# T08-TxClicker.net
KiCad netlist of a schematic drawn in EAGLE
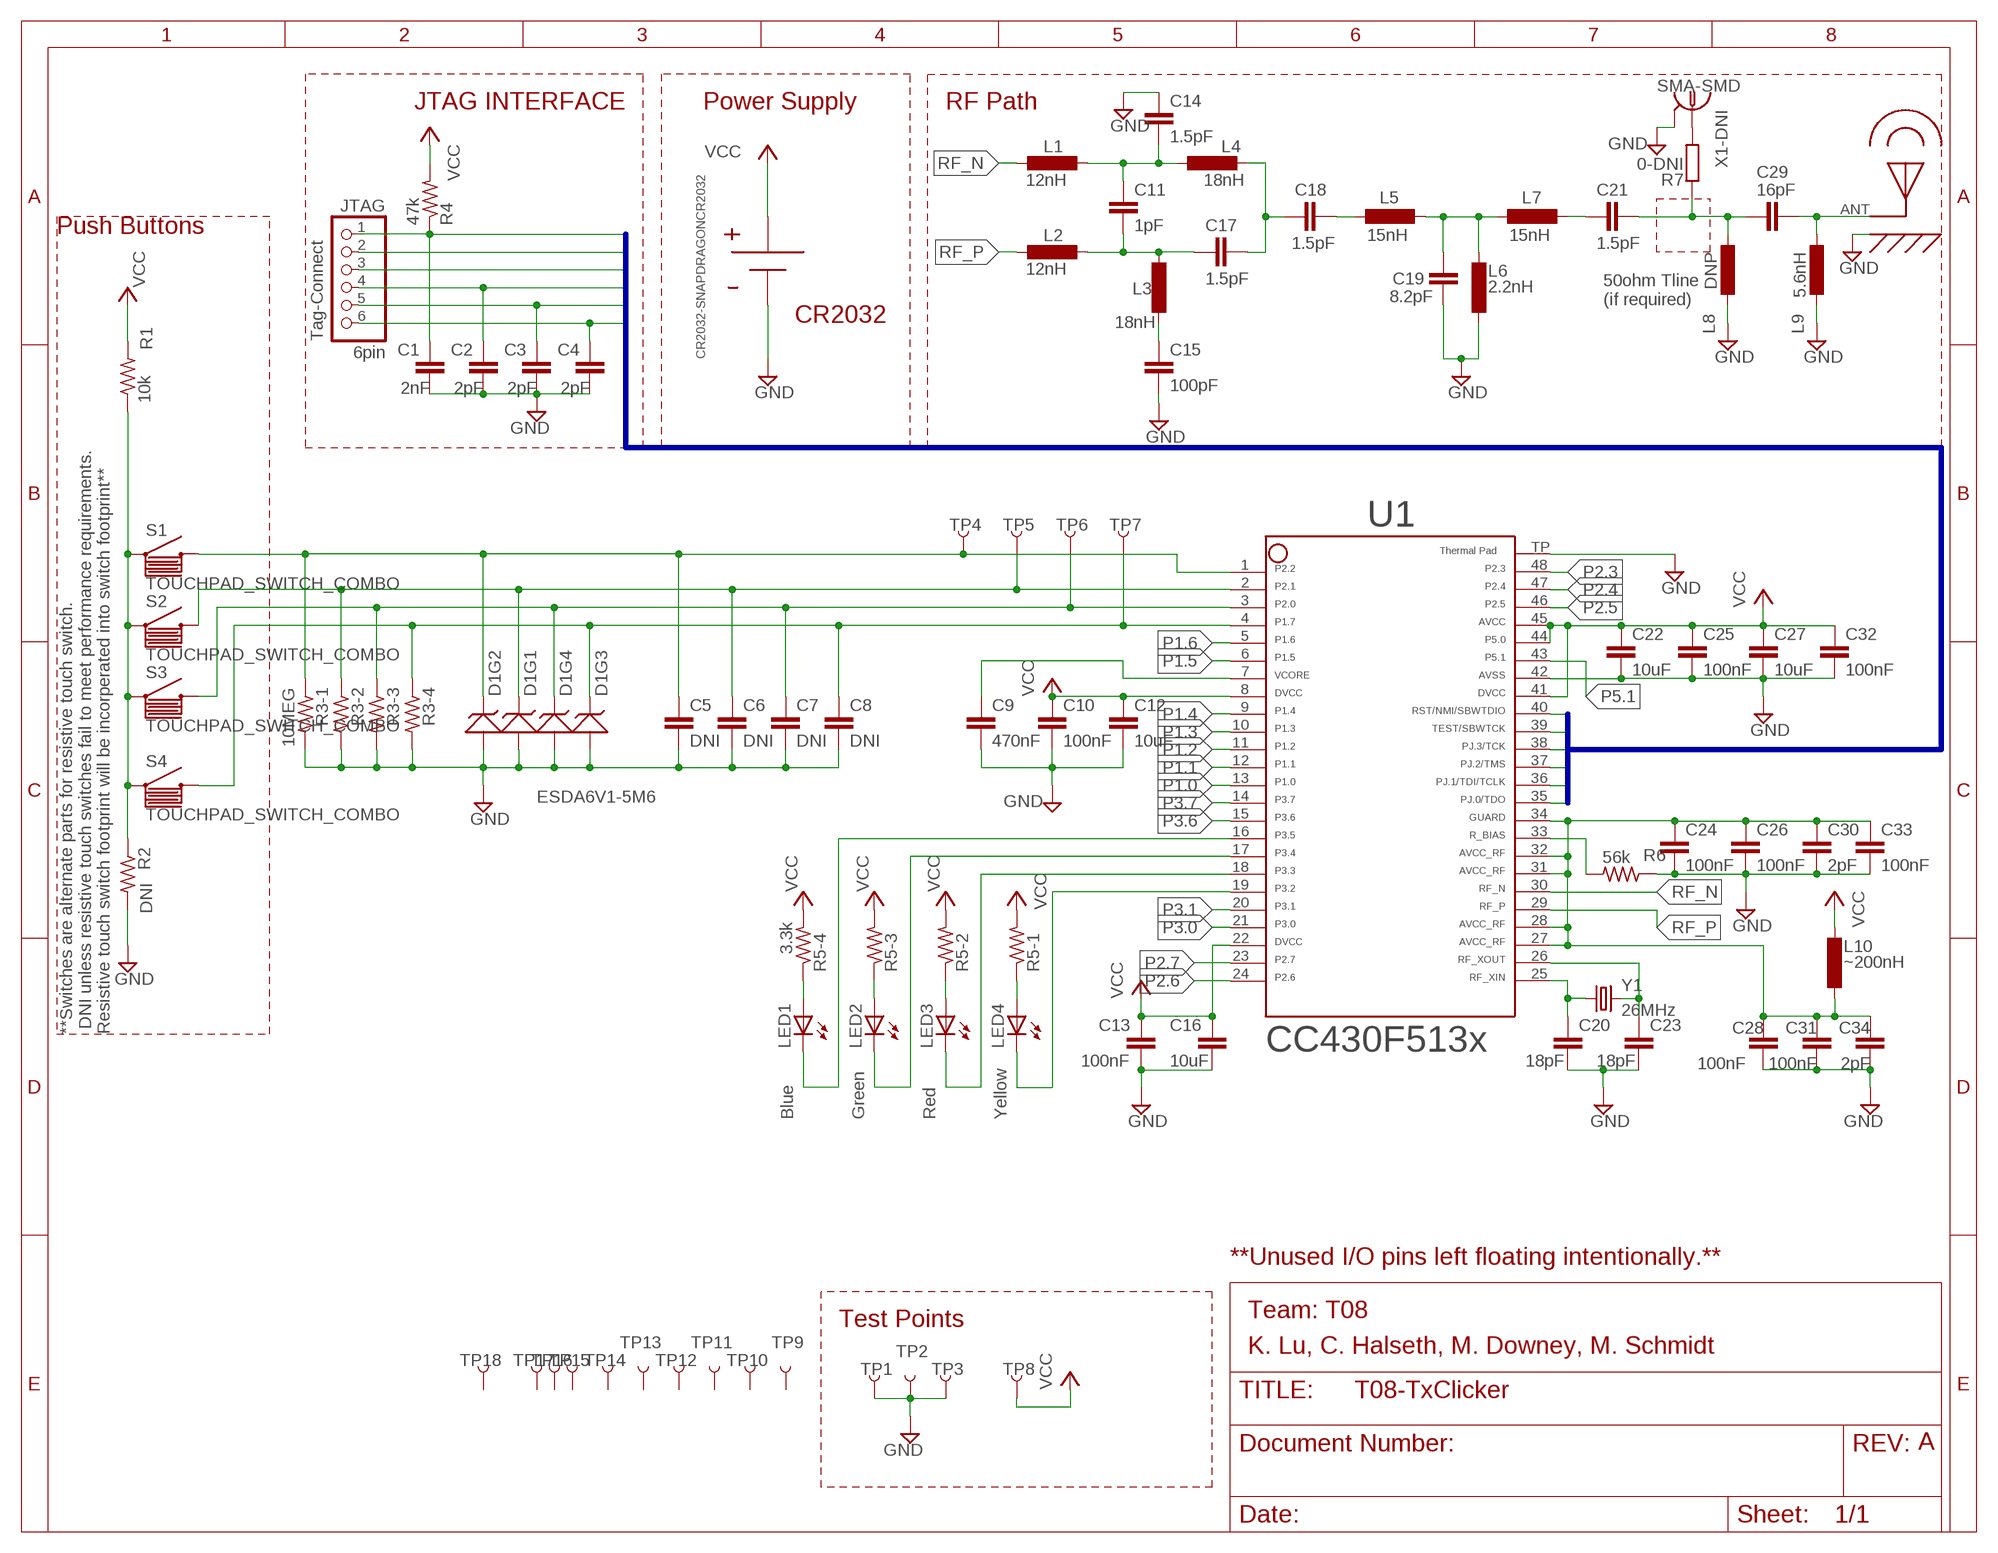
[diagram p0: schematic, sheet 1]

(export (version "E")
  (design (tool "Eeschema 10.0.6"))
  (components
    (comp (ref "C1")
      (value "2nF")
      (footprint "eagle-import:C0603")
      (libsource (lib "eagle-import") (part "C0603"))
    )
    (comp (ref "C2")
      (value "2pF")
      (footprint "eagle-import:C0603")
      (libsource (lib "eagle-import") (part "C0603"))
    )
    (comp (ref "C3")
      (value "2pF")
      (footprint "eagle-import:C0603")
      (libsource (lib "eagle-import") (part "C0603"))
    )
    (comp (ref "C4")
      (value "2pF")
      (footprint "eagle-import:C0603")
      (libsource (lib "eagle-import") (part "C0603"))
    )
    (comp (ref "C5")
      (value "DNI")
      (footprint "eagle-import:C0603")
      (libsource (lib "eagle-import") (part "C-EUC0603"))
    )
    (comp (ref "C6")
      (value "DNI")
      (footprint "eagle-import:C0603")
      (libsource (lib "eagle-import") (part "C-EUC0603"))
    )
    (comp (ref "C7")
      (value "DNI")
      (footprint "eagle-import:C0603")
      (libsource (lib "eagle-import") (part "C-EUC0603"))
    )
    (comp (ref "C8")
      (value "DNI")
      (footprint "eagle-import:C0603")
      (libsource (lib "eagle-import") (part "C-EUC0603"))
    )
    (comp (ref "C9")
      (value "470nF")
      (footprint "eagle-import:C0603")
      (libsource (lib "eagle-import") (part "C-EUC0603"))
    )
    (comp (ref "C10")
      (value "100nF")
      (footprint "eagle-import:C0603")
      (libsource (lib "eagle-import") (part "C-EUC0603"))
    )
    (comp (ref "C11")
      (value "1pF")
      (footprint "eagle-import:C0402")
      (libsource (lib "eagle-import") (part "C0402"))
    )
    (comp (ref "C12")
      (value "10uF")
      (footprint "eagle-import:C0805")
      (libsource (lib "eagle-import") (part "C-EUC0805"))
    )
    (comp (ref "C13")
      (value "100nF")
      (footprint "eagle-import:C0603")
      (libsource (lib "eagle-import") (part "C-EUC0603"))
    )
    (comp (ref "C14")
      (value "1.5pF")
      (footprint "eagle-import:C0402")
      (libsource (lib "eagle-import") (part "C0402"))
    )
    (comp (ref "C15")
      (value "100pF")
      (footprint "eagle-import:C0402")
      (libsource (lib "eagle-import") (part "C0402"))
    )
    (comp (ref "C16")
      (value "10uF")
      (footprint "eagle-import:C0805")
      (libsource (lib "eagle-import") (part "C-EUC0805"))
    )
    (comp (ref "C17")
      (value "1.5pF")
      (footprint "eagle-import:C0402")
      (libsource (lib "eagle-import") (part "C0402"))
    )
    (comp (ref "C18")
      (value "1.5pF")
      (footprint "eagle-import:C0402")
      (libsource (lib "eagle-import") (part "C0402"))
    )
    (comp (ref "C19")
      (value "8.2pF")
      (footprint "eagle-import:C0402")
      (libsource (lib "eagle-import") (part "C0402"))
    )
    (comp (ref "C20")
      (value "18pF")
      (footprint "eagle-import:C0402")
      (libsource (lib "eagle-import") (part "C-EUC0402"))
    )
    (comp (ref "C21")
      (value "1.5pF")
      (footprint "eagle-import:C0402")
      (libsource (lib "eagle-import") (part "C0402"))
    )
    (comp (ref "C22")
      (value "10uF")
      (footprint "eagle-import:C0805")
      (libsource (lib "eagle-import") (part "C-EUC0805"))
    )
    (comp (ref "C23")
      (value "18pF")
      (footprint "eagle-import:C0402")
      (libsource (lib "eagle-import") (part "C-EUC0402"))
    )
    (comp (ref "C24")
      (value "100nF")
      (footprint "eagle-import:C0603")
      (libsource (lib "eagle-import") (part "C-EUC0603"))
    )
    (comp (ref "C25")
      (value "100nF")
      (footprint "eagle-import:C0603")
      (libsource (lib "eagle-import") (part "C-EUC0603"))
    )
    (comp (ref "C26")
      (value "100nF")
      (footprint "eagle-import:C0603")
      (libsource (lib "eagle-import") (part "C-EUC0603"))
    )
    (comp (ref "C27")
      (value "10uF")
      (footprint "eagle-import:C0805")
      (libsource (lib "eagle-import") (part "C-EUC0805"))
    )
    (comp (ref "C28")
      (value "100nF")
      (footprint "eagle-import:C0603")
      (libsource (lib "eagle-import") (part "C-EUC0603"))
    )
    (comp (ref "C29")
      (value "16pF")
      (footprint "eagle-import:C0402")
      (libsource (lib "eagle-import") (part "C0402"))
    )
    (comp (ref "C30")
      (value "2pF")
      (footprint "eagle-import:C0603")
      (libsource (lib "eagle-import") (part "C-EUC0603"))
    )
    (comp (ref "C31")
      (value "100nF")
      (footprint "eagle-import:C0603")
      (libsource (lib "eagle-import") (part "C-EUC0603"))
    )
    (comp (ref "C32")
      (value "100nF")
      (footprint "eagle-import:C0603")
      (libsource (lib "eagle-import") (part "C-EUC0603"))
    )
    (comp (ref "C33")
      (value "100nF")
      (footprint "eagle-import:C0603")
      (libsource (lib "eagle-import") (part "C-EUC0603"))
    )
    (comp (ref "C34")
      (value "2pF")
      (footprint "eagle-import:C0603")
      (libsource (lib "eagle-import") (part "C-EUC0603"))
    )
    (comp (ref "D1")
      (value "ESDA6V1-5M6")
      (footprint "eagle-import:5X-TVS")
      (libsource (lib "eagle-import") (part "ESDA6V1-5M6"))
    )
    (comp (ref "JTAG")
      (value "6pin")
      (footprint "eagle-import:1X06")
      (libsource (lib "eagle-import") (part "PINHD-1X6"))
    )
    (comp (ref "L1")
      (value "12nH")
      (footprint "eagle-import:L0402")
      (libsource (lib "eagle-import") (part "LL0402"))
    )
    (comp (ref "L2")
      (value "12nH")
      (footprint "eagle-import:L0402")
      (libsource (lib "eagle-import") (part "LL0402"))
    )
    (comp (ref "L3")
      (value "18nH")
      (footprint "eagle-import:L0402")
      (libsource (lib "eagle-import") (part "LL0402"))
    )
    (comp (ref "L4")
      (value "18nH")
      (footprint "eagle-import:L0402")
      (libsource (lib "eagle-import") (part "LL0402"))
    )
    (comp (ref "L5")
      (value "15nH")
      (footprint "eagle-import:L0402")
      (libsource (lib "eagle-import") (part "LL0402"))
    )
    (comp (ref "L6")
      (value "2.2nH")
      (footprint "eagle-import:L0402")
      (libsource (lib "eagle-import") (part "LL0402"))
    )
    (comp (ref "L7")
      (value "15nH")
      (footprint "eagle-import:L0402")
      (libsource (lib "eagle-import") (part "LL0402"))
    )
    (comp (ref "L8")
      (value "DNP")
      (footprint "eagle-import:L0402")
      (libsource (lib "eagle-import") (part "LL0402"))
    )
    (comp (ref "L9")
      (value "5.6nH")
      (footprint "eagle-import:L0402")
      (libsource (lib "eagle-import") (part "LL0402"))
    )
    (comp (ref "L10")
      (value "~200nH")
      (footprint "eagle-import:L0603")
      (libsource (lib "eagle-import") (part "LL0603"))
    )
    (comp (ref "LED1")
      (value "Blue")
      (footprint "eagle-import:CHIP-LED0603")
      (libsource (lib "eagle-import") (part "LEDCHIP-LED0603"))
    )
    (comp (ref "LED2")
      (value "Green")
      (footprint "eagle-import:CHIP-LED0603")
      (libsource (lib "eagle-import") (part "LEDCHIP-LED0603"))
    )
    (comp (ref "LED3")
      (value "Red")
      (footprint "eagle-import:CHIP-LED0603")
      (libsource (lib "eagle-import") (part "LEDCHIP-LED0603"))
    )
    (comp (ref "LED4")
      (value "Yellow")
      (footprint "eagle-import:CHIP-LED0603")
      (libsource (lib "eagle-import") (part "LEDCHIP-LED0603"))
    )
    (comp (ref "R1")
      (value "10k")
      (footprint "eagle-import:R0603")
      (libsource (lib "eagle-import") (part "R-US_R0603"))
    )
    (comp (ref "R2")
      (value "DNI")
      (footprint "eagle-import:R0603")
      (libsource (lib "eagle-import") (part "R-US_R0603"))
    )
    (comp (ref "R3")
      (value "10MEG")
      (footprint "eagle-import:2012(4_RES)")
      (libsource (lib "eagle-import") (part "R603X42012"))
    )
    (comp (ref "R4")
      (value "47k")
      (footprint "eagle-import:R0603")
      (libsource (lib "eagle-import") (part "R-US_R0603"))
    )
    (comp (ref "R5")
      (value "3.3k")
      (footprint "eagle-import:2012(4_RES)")
      (libsource (lib "eagle-import") (part "R603X42012"))
    )
    (comp (ref "R6")
      (value "56k")
      (footprint "eagle-import:R0603")
      (libsource (lib "eagle-import") (part "R-US_R0603"))
    )
    (comp (ref "R7")
      (value "0-DNI")
      (footprint "eagle-import:R0603")
      (libsource (lib "eagle-import") (part "R0603"))
    )
    (comp (ref "S1")
      (value "TOUCHPAD_SWITCH_COMBO")
      (footprint "eagle-import:TACTILE-PTH-12MM")
      (libsource (lib "eagle-import") (part "TOUCHPAD_SWITCH_COMBO"))
    )
    (comp (ref "S2")
      (value "TOUCHPAD_SWITCH_COMBO")
      (footprint "eagle-import:TACTILE-PTH-12MM")
      (libsource (lib "eagle-import") (part "TOUCHPAD_SWITCH_COMBO"))
    )
    (comp (ref "S3")
      (value "TOUCHPAD_SWITCH_COMBO")
      (footprint "eagle-import:TACTILE-PTH-12MM")
      (libsource (lib "eagle-import") (part "TOUCHPAD_SWITCH_COMBO"))
    )
    (comp (ref "S4")
      (value "TOUCHPAD_SWITCH_COMBO")
      (footprint "eagle-import:TACTILE-PTH-12MM")
      (libsource (lib "eagle-import") (part "TOUCHPAD_SWITCH_COMBO"))
    )
    (comp (ref "TP1")
      (value "TEST-POINT3")
      (footprint "eagle-import:PAD.03X.03")
      (libsource (lib "eagle-import") (part "TEST-POINT3"))
    )
    (comp (ref "TP2")
      (value "TEST-POINT3")
      (footprint "eagle-import:PAD.03X.03")
      (libsource (lib "eagle-import") (part "TEST-POINT3"))
    )
    (comp (ref "TP3")
      (value "TEST-POINT3")
      (footprint "eagle-import:PAD.03X.03")
      (libsource (lib "eagle-import") (part "TEST-POINT3"))
    )
    (comp (ref "TP4")
      (value "TEST-POINT3")
      (footprint "eagle-import:PAD.03X.03")
      (libsource (lib "eagle-import") (part "TEST-POINT3"))
    )
    (comp (ref "TP5")
      (value "TEST-POINT3")
      (footprint "eagle-import:PAD.03X.03")
      (libsource (lib "eagle-import") (part "TEST-POINT3"))
    )
    (comp (ref "TP6")
      (value "TEST-POINT3")
      (footprint "eagle-import:PAD.03X.03")
      (libsource (lib "eagle-import") (part "TEST-POINT3"))
    )
    (comp (ref "TP7")
      (value "TEST-POINT3")
      (footprint "eagle-import:PAD.03X.03")
      (libsource (lib "eagle-import") (part "TEST-POINT3"))
    )
    (comp (ref "TP8")
      (value "TEST-POINT3")
      (footprint "eagle-import:PAD.03X.03")
      (libsource (lib "eagle-import") (part "TEST-POINT3"))
    )
    (comp (ref "TP9")
      (value "TEST-POINT3")
      (footprint "eagle-import:PAD.03X.03")
      (libsource (lib "eagle-import") (part "TEST-POINT3"))
    )
    (comp (ref "TP10")
      (value "TEST-POINT3")
      (footprint "eagle-import:PAD.03X.03")
      (libsource (lib "eagle-import") (part "TEST-POINT3"))
    )
    (comp (ref "TP11")
      (value "TEST-POINT3")
      (footprint "eagle-import:PAD.03X.03")
      (libsource (lib "eagle-import") (part "TEST-POINT3"))
    )
    (comp (ref "TP12")
      (value "TEST-POINT3")
      (footprint "eagle-import:PAD.03X.03")
      (libsource (lib "eagle-import") (part "TEST-POINT3"))
    )
    (comp (ref "TP13")
      (value "TEST-POINT3")
      (footprint "eagle-import:PAD.03X.03")
      (libsource (lib "eagle-import") (part "TEST-POINT3"))
    )
    (comp (ref "TP14")
      (value "TEST-POINT3")
      (footprint "eagle-import:PAD.03X.03")
      (libsource (lib "eagle-import") (part "TEST-POINT3"))
    )
    (comp (ref "TP15")
      (value "TEST-POINT3")
      (footprint "eagle-import:PAD.03X.03")
      (libsource (lib "eagle-import") (part "TEST-POINT3"))
    )
    (comp (ref "TP16")
      (value "TEST-POINT3")
      (footprint "eagle-import:PAD.03X.03")
      (libsource (lib "eagle-import") (part "TEST-POINT3"))
    )
    (comp (ref "TP17")
      (value "TEST-POINT3")
      (footprint "eagle-import:PAD.03X.03")
      (libsource (lib "eagle-import") (part "TEST-POINT3"))
    )
    (comp (ref "TP18")
      (value "TEST-POINT3")
      (footprint "eagle-import:PAD.03X.03")
      (libsource (lib "eagle-import") (part "TEST-POINT3"))
    )
    (comp (ref "U$5")
      (value "CR2032-SNAPDRAGONCR2032")
      (footprint "eagle-import:CR2032-SNAPDRAGON")
      (libsource (lib "eagle-import") (part "CR2032-SNAPDRAGONCR2032"))
    )
    (comp (ref "U$6")
      (value "PCB_ANTENNA_915MHZOSHP")
      (footprint "eagle-import:PCB_ANTENNA_915MHZ")
      (libsource (lib "eagle-import") (part "PCB_ANTENNA_915MHZOSHP"))
    )
    (comp (ref "U1")
      (value "CC430F513X---RGZ48")
      (footprint "eagle-import:RGZ48")
      (libsource (lib "eagle-import") (part "CC430F513X---RGZ48"))
    )
    (comp (ref "X1-DNI")
      (value "SMA-SMD")
      (footprint "eagle-import:SMA-SMD")
      (libsource (lib "eagle-import") (part "SMA-SMD"))
    )
    (comp (ref "Y1")
      (value "26MHz")
      (footprint "eagle-import:CRYSTAL-TXC-7A")
      (libsource (lib "eagle-import") (part "CRYSTALTXC-7A"))
    )
  )
  (nets
    (net (code "1") (name "/PJ.0{slash}TDO") (class "Default")
      (node (ref "C4") (pin "1") (pinfunction "1_1") (pintype "passive"))
      (node (ref "JTAG") (pin "6") (pinfunction "6_6") (pintype "passive"))
      (node (ref "U1") (pin "35") (pinfunction "35_35") (pintype "bidirectional"))
    )
    (net (code "2") (name "/PJ.1{slash}TDI{slash}TCLK") (class "Default")
      (node (ref "C3") (pin "1") (pinfunction "1_1") (pintype "passive"))
      (node (ref "JTAG") (pin "5") (pinfunction "5_5") (pintype "passive"))
      (node (ref "U1") (pin "36") (pinfunction "36_36") (pintype "bidirectional"))
    )
    (net (code "3") (name "/PJ.2{slash}TMS") (class "Default")
      (node (ref "C2") (pin "1") (pinfunction "1_1") (pintype "passive"))
      (node (ref "JTAG") (pin "4") (pinfunction "4_4") (pintype "passive"))
      (node (ref "U1") (pin "37") (pinfunction "37_37") (pintype "bidirectional"))
    )
    (net (code "4") (name "/PJ.3{slash}TCK") (class "Default")
      (node (ref "JTAG") (pin "3") (pinfunction "3_3") (pintype "passive"))
      (node (ref "U1") (pin "38") (pinfunction "38_38") (pintype "bidirectional"))
    )
    (net (code "5") (name "/RST{slash}NMI{slash}SBWTDIO") (class "Default")
      (node (ref "C1") (pin "1") (pinfunction "1_1") (pintype "passive"))
      (node (ref "JTAG") (pin "1") (pinfunction "1_1") (pintype "passive"))
      (node (ref "R4") (pin "1") (pinfunction "1_1") (pintype "passive"))
      (node (ref "U1") (pin "40") (pinfunction "40_40") (pintype "bidirectional"))
    )
    (net (code "6") (name "/TEST{slash}SBWTCK") (class "Default")
      (node (ref "JTAG") (pin "2") (pinfunction "2_2") (pintype "passive"))
      (node (ref "U1") (pin "39") (pinfunction "39_39") (pintype "input"))
    )
    (net (code "7") (name "GND") (class "Default")
      (node (ref "C1") (pin "2") (pinfunction "2_2") (pintype "passive"))
      (node (ref "C10") (pin "2") (pinfunction "2_2") (pintype "passive"))
      (node (ref "C12") (pin "2") (pinfunction "2_2") (pintype "passive"))
      (node (ref "C13") (pin "2") (pinfunction "2_2") (pintype "passive"))
      (node (ref "C14") (pin "P$1") (pinfunction "1_P$1") (pintype "passive"))
      (node (ref "C15") (pin "P$2") (pinfunction "2_P$2") (pintype "passive"))
      (node (ref "C16") (pin "2") (pinfunction "2_2") (pintype "passive"))
      (node (ref "C19") (pin "P$1") (pinfunction "1_P$1") (pintype "passive"))
      (node (ref "C2") (pin "2") (pinfunction "2_2") (pintype "passive"))
      (node (ref "C20") (pin "2") (pinfunction "2_2") (pintype "passive"))
      (node (ref "C22") (pin "2") (pinfunction "2_2") (pintype "passive"))
      (node (ref "C23") (pin "2") (pinfunction "2_2") (pintype "passive"))
      (node (ref "C24") (pin "2") (pinfunction "2_2") (pintype "passive"))
      (node (ref "C25") (pin "2") (pinfunction "2_2") (pintype "passive"))
      (node (ref "C26") (pin "2") (pinfunction "2_2") (pintype "passive"))
      (node (ref "C27") (pin "2") (pinfunction "2_2") (pintype "passive"))
      (node (ref "C28") (pin "2") (pinfunction "2_2") (pintype "passive"))
      (node (ref "C3") (pin "2") (pinfunction "2_2") (pintype "passive"))
      (node (ref "C30") (pin "2") (pinfunction "2_2") (pintype "passive"))
      (node (ref "C31") (pin "2") (pinfunction "2_2") (pintype "passive"))
      (node (ref "C32") (pin "2") (pinfunction "2_2") (pintype "passive"))
      (node (ref "C33") (pin "2") (pinfunction "2_2") (pintype "passive"))
      (node (ref "C34") (pin "2") (pinfunction "2_2") (pintype "passive"))
      (node (ref "C4") (pin "2") (pinfunction "2_2") (pintype "passive"))
      (node (ref "C5") (pin "2") (pinfunction "2_2") (pintype "passive"))
      (node (ref "C6") (pin "2") (pinfunction "2_2") (pintype "passive"))
      (node (ref "C7") (pin "2") (pinfunction "2_2") (pintype "passive"))
      (node (ref "C8") (pin "2") (pinfunction "2_2") (pintype "passive"))
      (node (ref "C9") (pin "2") (pinfunction "2_2") (pintype "passive"))
      (node (ref "D1") (pin "2") (pinfunction "2_2") (pintype "bidirectional"))
      (node (ref "L6") (pin "P$2") (pinfunction "2_P$2") (pintype "passive"))
      (node (ref "L8") (pin "P$1") (pinfunction "1_P$1") (pintype "passive"))
      (node (ref "L9") (pin "P$1") (pinfunction "1_P$1") (pintype "passive"))
      (node (ref "R2") (pin "2") (pinfunction "2_2") (pintype "passive"))
      (node (ref "R3") (pin "2") (pinfunction "2_2") (pintype "passive"))
      (node (ref "R3") (pin "4") (pinfunction "2_4") (pintype "passive"))
      (node (ref "R3") (pin "6") (pinfunction "2_6") (pintype "passive"))
      (node (ref "R3") (pin "8") (pinfunction "2_8") (pintype "passive"))
      (node (ref "R6") (pin "1") (pinfunction "1_1") (pintype "passive"))
      (node (ref "TP1") (pin "P$1") (pinfunction "1_P$1") (pintype "bidirectional"))
      (node (ref "TP2") (pin "P$1") (pinfunction "1_P$1") (pintype "bidirectional"))
      (node (ref "TP3") (pin "P$1") (pinfunction "1_P$1") (pintype "bidirectional"))
      (node (ref "U$5") (pin "V-") (pinfunction "V-_V-") (pintype "power_in"))
      (node (ref "U$6") (pin "GPLANE") (pinfunction "GPLANE_GPLANE") (pintype "power_in"))
      (node (ref "U1") (pin "42") (pinfunction "42_42") (pintype "power_in"))
      (node (ref "U1") (pin "TP") (pinfunction "49_TP") (pintype "power_in"))
      (node (ref "X1-DNI") (pin "2@1") (pinfunction "2_2@1") (pintype "passive"))
      (node (ref "X1-DNI") (pin "2@2") (pinfunction "2_2@2") (pintype "passive"))
      (node (ref "X1-DNI") (pin "2@3") (pinfunction "2_2@3") (pintype "passive"))
      (node (ref "X1-DNI") (pin "2@4") (pinfunction "2_2@4") (pintype "passive"))
      (node (ref "X1-DNI") (pin "2@5") (pinfunction "2_2@5") (pintype "passive"))
      (node (ref "X1-DNI") (pin "2@6") (pinfunction "2_2@6") (pintype "passive"))
    )
    (net (code "8") (name "Net-(C9-Pad1)") (class "Default")
      (node (ref "C9") (pin "1") (pinfunction "1_1") (pintype "passive"))
      (node (ref "U1") (pin "7") (pinfunction "7_7") (pintype "power_in"))
    )
    (net (code "9") (name "Net-(C11-1)") (class "Default")
      (node (ref "C11") (pin "P$1") (pinfunction "1_P$1") (pintype "passive"))
      (node (ref "C14") (pin "P$2") (pinfunction "2_P$2") (pintype "passive"))
      (node (ref "L1") (pin "P$1") (pinfunction "1_P$1") (pintype "passive"))
      (node (ref "L4") (pin "P$2") (pinfunction "2_P$2") (pintype "passive"))
    )
    (net (code "10") (name "Net-(C11-2)") (class "Default")
      (node (ref "C11") (pin "P$2") (pinfunction "2_P$2") (pintype "passive"))
      (node (ref "C17") (pin "P$2") (pinfunction "2_P$2") (pintype "passive"))
      (node (ref "L2") (pin "P$1") (pinfunction "1_P$1") (pintype "passive"))
      (node (ref "L3") (pin "P$1") (pinfunction "1_P$1") (pintype "passive"))
    )
    (net (code "11") (name "Net-(C15-1)") (class "Default")
      (node (ref "C15") (pin "P$1") (pinfunction "1_P$1") (pintype "passive"))
      (node (ref "L3") (pin "P$2") (pinfunction "2_P$2") (pintype "passive"))
    )
    (net (code "12") (name "Net-(C17-1)") (class "Default")
      (node (ref "C17") (pin "P$1") (pinfunction "1_P$1") (pintype "passive"))
      (node (ref "C18") (pin "P$1") (pinfunction "1_P$1") (pintype "passive"))
      (node (ref "L4") (pin "P$1") (pinfunction "1_P$1") (pintype "passive"))
    )
    (net (code "13") (name "Net-(C18-2)") (class "Default")
      (node (ref "C18") (pin "P$2") (pinfunction "2_P$2") (pintype "passive"))
      (node (ref "L5") (pin "P$1") (pinfunction "1_P$1") (pintype "passive"))
    )
    (net (code "14") (name "Net-(C19-2)") (class "Default")
      (node (ref "C19") (pin "P$2") (pinfunction "2_P$2") (pintype "passive"))
      (node (ref "L5") (pin "P$2") (pinfunction "2_P$2") (pintype "passive"))
      (node (ref "L6") (pin "P$1") (pinfunction "1_P$1") (pintype "passive"))
      (node (ref "L7") (pin "P$1") (pinfunction "1_P$1") (pintype "passive"))
    )
    (net (code "15") (name "Net-(C21-1)") (class "Default")
      (node (ref "C21") (pin "P$1") (pinfunction "1_P$1") (pintype "passive"))
      (node (ref "C29") (pin "P$2") (pinfunction "2_P$2") (pintype "passive"))
      (node (ref "L8") (pin "P$2") (pinfunction "2_P$2") (pintype "passive"))
      (node (ref "R7") (pin "1") (pinfunction "1_1") (pintype "passive"))
    )
    (net (code "16") (name "Net-(C21-2)") (class "Default")
      (node (ref "C21") (pin "P$2") (pinfunction "2_P$2") (pintype "passive"))
      (node (ref "L7") (pin "P$2") (pinfunction "2_P$2") (pintype "passive"))
    )
    (net (code "17") (name "Net-(C24-Pad1)") (class "Default")
      (node (ref "C24") (pin "1") (pinfunction "1_1") (pintype "passive"))
      (node (ref "C26") (pin "1") (pinfunction "1_1") (pintype "passive"))
      (node (ref "C28") (pin "1") (pinfunction "1_1") (pintype "passive"))
      (node (ref "C30") (pin "1") (pinfunction "1_1") (pintype "passive"))
      (node (ref "C31") (pin "1") (pinfunction "1_1") (pintype "passive"))
      (node (ref "C33") (pin "1") (pinfunction "1_1") (pintype "passive"))
      (node (ref "C34") (pin "1") (pinfunction "1_1") (pintype "passive"))
      (node (ref "L10") (pin "2") (pinfunction "2_2") (pintype "passive"))
      (node (ref "U1") (pin "27") (pinfunction "27_27") (pintype "power_in"))
      (node (ref "U1") (pin "28") (pinfunction "28_28") (pintype "bidirectional"))
      (node (ref "U1") (pin "31") (pinfunction "31_31") (pintype "power_in"))
      (node (ref "U1") (pin "32") (pinfunction "32_32") (pintype "power_in"))
      (node (ref "U1") (pin "34") (pinfunction "34_34") (pintype "power_in"))
    )
    (net (code "18") (name "Net-(C29-1)") (class "Default")
      (node (ref "C29") (pin "P$1") (pinfunction "1_P$1") (pintype "passive"))
      (node (ref "L9") (pin "P$2") (pinfunction "2_P$2") (pintype "passive"))
      (node (ref "U$6") (pin "ANT") (pinfunction "ANT_ANT") (pintype "input"))
    )
    (net (code "19") (name "Net-(D1B-P$1)") (class "Default")
      (node (ref "C5") (pin "1") (pinfunction "1_1") (pintype "passive"))
      (node (ref "D1") (pin "3") (pinfunction "P$1_3") (pintype "bidirectional"))
      (node (ref "R3") (pin "1") (pinfunction "1_1") (pintype "passive"))
      (node (ref "S1") (pin "3") (pinfunction "2_3") (pintype "passive"))
      (node (ref "TP4") (pin "P$1") (pinfunction "1_P$1") (pintype "bidirectional"))
      (node (ref "U1") (pin "1") (pinfunction "1_1") (pintype "bidirectional"))
    )
    (net (code "20") (name "Net-(D1C-P$1)") (class "Default")
      (node (ref "C8") (pin "1") (pinfunction "1_1") (pintype "passive"))
      (node (ref "D1") (pin "4") (pinfunction "P$1_4") (pintype "bidirectional"))
      (node (ref "R3") (pin "7") (pinfunction "1_7") (pintype "passive"))
      (node (ref "S4") (pin "3") (pinfunction "2_3") (pintype "passive"))
      (node (ref "TP7") (pin "P$1") (pinfunction "1_P$1") (pintype "bidirectional"))
      (node (ref "U1") (pin "4") (pinfunction "4_4") (pintype "bidirectional"))
    )
    (net (code "21") (name "Net-(D1D-P$1)") (class "Default")
      (node (ref "C7") (pin "1") (pinfunction "1_1") (pintype "passive"))
      (node (ref "D1") (pin "5") (pinfunction "P$1_5") (pintype "bidirectional"))
      (node (ref "R3") (pin "5") (pinfunction "1_5") (pintype "passive"))
      (node (ref "S3") (pin "3") (pinfunction "2_3") (pintype "passive"))
      (node (ref "TP6") (pin "P$1") (pinfunction "1_P$1") (pintype "bidirectional"))
      (node (ref "U1") (pin "3") (pinfunction "3_3") (pintype "bidirectional"))
    )
    (net (code "22") (name "Net-(LED1-PadC)") (class "Default")
      (node (ref "LED1") (pin "C") (pinfunction "C_C") (pintype "bidirectional"))
      (node (ref "U1") (pin "16") (pinfunction "16_16") (pintype "bidirectional"))
    )
    (net (code "23") (name "Net-(LED2-PadC)") (class "Default")
      (node (ref "LED2") (pin "C") (pinfunction "C_C") (pintype "bidirectional"))
      (node (ref "U1") (pin "17") (pinfunction "17_17") (pintype "bidirectional"))
    )
    (net (code "24") (name "Net-(LED3-PadC)") (class "Default")
      (node (ref "LED3") (pin "C") (pinfunction "C_C") (pintype "bidirectional"))
      (node (ref "U1") (pin "18") (pinfunction "18_18") (pintype "bidirectional"))
    )
    (net (code "25") (name "Net-(LED4-PadA)") (class "Default")
      (node (ref "LED4") (pin "A") (pinfunction "A_A") (pintype "bidirectional"))
      (node (ref "R5") (pin "1") (pinfunction "1_1") (pintype "passive"))
    )
    (net (code "26") (name "Net-(LED4-PadC)") (class "Default")
      (node (ref "LED4") (pin "C") (pinfunction "C_C") (pintype "bidirectional"))
      (node (ref "U1") (pin "19") (pinfunction "19_19") (pintype "bidirectional"))
    )
    (net (code "27") (name "Net-(R1-Pad1)") (class "Default")
      (node (ref "R1") (pin "1") (pinfunction "1_1") (pintype "passive"))
      (node (ref "R2") (pin "1") (pinfunction "1_1") (pintype "passive"))
      (node (ref "S1") (pin "1") (pinfunction "1_1") (pintype "passive"))
      (node (ref "S2") (pin "1") (pinfunction "1_1") (pintype "passive"))
      (node (ref "S3") (pin "1") (pinfunction "1_1") (pintype "passive"))
      (node (ref "S4") (pin "1") (pinfunction "1_1") (pintype "passive"))
    )
    (net (code "28") (name "Net-(R3B-1)") (class "Default")
      (node (ref "C6") (pin "1") (pinfunction "1_1") (pintype "passive"))
      (node (ref "D1") (pin "1") (pinfunction "1_1") (pintype "bidirectional"))
      (node (ref "R3") (pin "3") (pinfunction "1_3") (pintype "passive"))
      (node (ref "S2") (pin "3") (pinfunction "2_3") (pintype "passive"))
      (node (ref "TP5") (pin "P$1") (pinfunction "1_P$1") (pintype "bidirectional"))
      (node (ref "U1") (pin "2") (pinfunction "2_2") (pintype "bidirectional"))
    )
    (net (code "29") (name "Net-(R5B-1)") (class "Default")
      (node (ref "LED3") (pin "A") (pinfunction "A_A") (pintype "bidirectional"))
      (node (ref "R5") (pin "3") (pinfunction "1_3") (pintype "passive"))
    )
    (net (code "30") (name "Net-(R5C-1)") (class "Default")
      (node (ref "LED2") (pin "A") (pinfunction "A_A") (pintype "bidirectional"))
      (node (ref "R5") (pin "5") (pinfunction "1_5") (pintype "passive"))
    )
    (net (code "31") (name "Net-(R5D-1)") (class "Default")
      (node (ref "LED1") (pin "A") (pinfunction "A_A") (pintype "bidirectional"))
      (node (ref "R5") (pin "7") (pinfunction "1_7") (pintype "passive"))
    )
    (net (code "32") (name "Net-(R6-Pad2)") (class "Default")
      (node (ref "R6") (pin "2") (pinfunction "2_2") (pintype "passive"))
      (node (ref "U1") (pin "33") (pinfunction "33_33") (pintype "power_in"))
    )
    (net (code "33") (name "Net-(R7-Pad2)") (class "Default")
      (node (ref "R7") (pin "2") (pinfunction "2_2") (pintype "passive"))
      (node (ref "X1-DNI") (pin "1") (pinfunction "1_1") (pintype "passive"))
    )
    (net (code "34") (name "Net-(Y1-1)") (class "Default")
      (node (ref "C20") (pin "1") (pinfunction "1_1") (pintype "passive"))
      (node (ref "U1") (pin "25") (pinfunction "25_25") (pintype "input"))
      (node (ref "Y1") (pin "P$1") (pinfunction "1_P$1") (pintype "passive"))
    )
    (net (code "35") (name "Net-(Y1-2)") (class "Default")
      (node (ref "C23") (pin "1") (pinfunction "1_1") (pintype "passive"))
      (node (ref "U1") (pin "26") (pinfunction "26_26") (pintype "output"))
      (node (ref "Y1") (pin "P$2") (pinfunction "2_P$2") (pintype "passive"))
    )
    (net (code "36") (name "P1.0") (class "Default")
      (node (ref "U1") (pin "13") (pinfunction "13_13") (pintype "bidirectional"))
    )
    (net (code "37") (name "P1.1") (class "Default")
      (node (ref "U1") (pin "12") (pinfunction "12_12") (pintype "bidirectional"))
    )
    (net (code "38") (name "P1.2") (class "Default")
      (node (ref "U1") (pin "11") (pinfunction "11_11") (pintype "bidirectional"))
    )
    (net (code "39") (name "P1.3") (class "Default")
      (node (ref "U1") (pin "10") (pinfunction "10_10") (pintype "bidirectional"))
    )
    (net (code "40") (name "P1.4") (class "Default")
      (node (ref "U1") (pin "9") (pinfunction "9_9") (pintype "bidirectional"))
    )
    (net (code "41") (name "P1.5") (class "Default")
      (node (ref "U1") (pin "6") (pinfunction "6_6") (pintype "bidirectional"))
    )
    (net (code "42") (name "P1.6") (class "Default")
      (node (ref "U1") (pin "5") (pinfunction "5_5") (pintype "bidirectional"))
    )
    (net (code "43") (name "P2.3") (class "Default")
      (node (ref "U1") (pin "48") (pinfunction "48_48") (pintype "bidirectional"))
    )
    (net (code "44") (name "P2.4") (class "Default")
      (node (ref "U1") (pin "47") (pinfunction "47_47") (pintype "bidirectional"))
    )
    (net (code "45") (name "P2.5") (class "Default")
      (node (ref "U1") (pin "46") (pinfunction "46_46") (pintype "bidirectional"))
    )
    (net (code "46") (name "P2.6") (class "Default")
      (node (ref "U1") (pin "24") (pinfunction "24_24") (pintype "bidirectional"))
    )
    (net (code "47") (name "P2.7") (class "Default")
      (node (ref "U1") (pin "23") (pinfunction "23_23") (pintype "bidirectional"))
    )
    (net (code "48") (name "P3.0") (class "Default")
      (node (ref "U1") (pin "21") (pinfunction "21_21") (pintype "bidirectional"))
    )
    (net (code "49") (name "P3.1") (class "Default")
      (node (ref "U1") (pin "20") (pinfunction "20_20") (pintype "bidirectional"))
    )
    (net (code "50") (name "P3.6") (class "Default")
      (node (ref "U1") (pin "15") (pinfunction "15_15") (pintype "bidirectional"))
    )
    (net (code "51") (name "P3.7") (class "Default")
      (node (ref "U1") (pin "14") (pinfunction "14_14") (pintype "bidirectional"))
    )
    (net (code "52") (name "P5.1") (class "Default")
      (node (ref "U1") (pin "43") (pinfunction "43_43") (pintype "bidirectional"))
    )
    (net (code "53") (name "RF_N") (class "Default")
      (node (ref "L1") (pin "P$2") (pinfunction "2_P$2") (pintype "passive"))
      (node (ref "U1") (pin "30") (pinfunction "30_30") (pintype "bidirectional"))
    )
    (net (code "54") (name "RF_P") (class "Default")
      (node (ref "L2") (pin "P$2") (pinfunction "2_P$2") (pintype "passive"))
      (node (ref "U1") (pin "29") (pinfunction "29_29") (pintype "bidirectional"))
    )
    (net (code "55") (name "VCC") (class "Default")
      (node (ref "C10") (pin "1") (pinfunction "1_1") (pintype "passive"))
      (node (ref "C12") (pin "1") (pinfunction "1_1") (pintype "passive"))
      (node (ref "C13") (pin "1") (pinfunction "1_1") (pintype "passive"))
      (node (ref "C16") (pin "1") (pinfunction "1_1") (pintype "passive"))
      (node (ref "C22") (pin "1") (pinfunction "1_1") (pintype "passive"))
      (node (ref "C25") (pin "1") (pinfunction "1_1") (pintype "passive"))
      (node (ref "C27") (pin "1") (pinfunction "1_1") (pintype "passive"))
      (node (ref "C32") (pin "1") (pinfunction "1_1") (pintype "passive"))
      (node (ref "L10") (pin "1") (pinfunction "1_1") (pintype "passive"))
      (node (ref "R1") (pin "2") (pinfunction "2_2") (pintype "passive"))
      (node (ref "R4") (pin "2") (pinfunction "2_2") (pintype "passive"))
      (node (ref "R5") (pin "2") (pinfunction "2_2") (pintype "passive"))
      (node (ref "R5") (pin "4") (pinfunction "2_4") (pintype "passive"))
      (node (ref "R5") (pin "6") (pinfunction "2_6") (pintype "passive"))
      (node (ref "R5") (pin "8") (pinfunction "2_8") (pintype "passive"))
      (node (ref "TP8") (pin "P$1") (pinfunction "1_P$1") (pintype "bidirectional"))
      (node (ref "U$5") (pin "V+") (pinfunction "V+_V+") (pintype "passive"))
      (node (ref "U1") (pin "22") (pinfunction "22_22") (pintype "power_in"))
      (node (ref "U1") (pin "41") (pinfunction "41_41") (pintype "power_in"))
      (node (ref "U1") (pin "44") (pinfunction "44_44") (pintype "input"))
      (node (ref "U1") (pin "45") (pinfunction "45_45") (pintype "input"))
      (node (ref "U1") (pin "8") (pinfunction "8_8") (pintype "power_in"))
    )
    (net (code "56") (name "unconnected-(TP9-1-PadP$1)") (class "Default")
      (node (ref "TP9") (pin "P$1") (pinfunction "1_P$1") (pintype "bidirectional"))
    )
    (net (code "57") (name "unconnected-(TP10-1-PadP$1)") (class "Default")
      (node (ref "TP10") (pin "P$1") (pinfunction "1_P$1") (pintype "bidirectional"))
    )
    (net (code "58") (name "unconnected-(TP11-1-PadP$1)") (class "Default")
      (node (ref "TP11") (pin "P$1") (pinfunction "1_P$1") (pintype "bidirectional"))
    )
    (net (code "59") (name "unconnected-(TP12-1-PadP$1)") (class "Default")
      (node (ref "TP12") (pin "P$1") (pinfunction "1_P$1") (pintype "bidirectional"))
    )
    (net (code "60") (name "unconnected-(TP13-1-PadP$1)") (class "Default")
      (node (ref "TP13") (pin "P$1") (pinfunction "1_P$1") (pintype "bidirectional"))
    )
    (net (code "61") (name "unconnected-(TP14-1-PadP$1)") (class "Default")
      (node (ref "TP14") (pin "P$1") (pinfunction "1_P$1") (pintype "bidirectional"))
    )
    (net (code "62") (name "unconnected-(TP15-1-PadP$1)") (class "Default")
      (node (ref "TP15") (pin "P$1") (pinfunction "1_P$1") (pintype "bidirectional"))
    )
    (net (code "63") (name "unconnected-(TP16-1-PadP$1)") (class "Default")
      (node (ref "TP16") (pin "P$1") (pinfunction "1_P$1") (pintype "bidirectional"))
    )
    (net (code "64") (name "unconnected-(TP17-1-PadP$1)") (class "Default")
      (node (ref "TP17") (pin "P$1") (pinfunction "1_P$1") (pintype "bidirectional"))
    )
    (net (code "65") (name "unconnected-(TP18-1-PadP$1)") (class "Default")
      (node (ref "TP18") (pin "P$1") (pinfunction "1_P$1") (pintype "bidirectional"))
    )
  )
)
